# Prova01.net
KiCad netlist of a schematic drawn in EAGLE
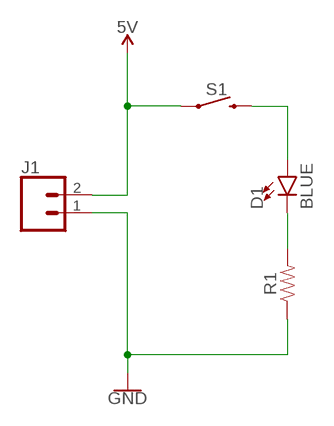
[diagram p0: schematic, sheet 1]

(export (version "E")
  (design (tool "Eeschema 10.0.6"))
  (components
    (comp (ref "D1")
      (value "BLUE")
      (footprint "eagle-import:LED-0603")
      (libsource (lib "eagle-import") (part "LED-BLUE0603"))
    )
    (comp (ref "J1")
      (value "CONN_02")
      (footprint "eagle-import:1X02")
      (libsource (lib "eagle-import") (part "CONN_02"))
    )
    (comp (ref "R1")
      (value "RESISTORAXIAL-0.3")
      (footprint "eagle-import:AXIAL-0.3")
      (libsource (lib "eagle-import") (part "RESISTORAXIAL-0.3"))
    )
    (comp (ref "S1")
      (value "MOMENTARY-SWITCH-SPST-PTH-6.0MM")
      (footprint "eagle-import:TACTILE_SWITCH_PTH_6.0MM")
      (libsource (lib "eagle-import") (part "MOMENTARY-SWITCH-SPST-PTH-6.0MM"))
    )
  )
  (nets
    (net (code "1") (name "5V") (class "Default")
      (node (ref "J1") (pin "2") (pinfunction "2_2") (pintype "passive"))
      (node (ref "S1") (pin "1") (pinfunction "1_1") (pintype "passive"))
    )
    (net (code "2") (name "GND") (class "Default")
      (node (ref "J1") (pin "1") (pinfunction "1_1") (pintype "passive"))
      (node (ref "R1") (pin "P$1") (pinfunction "1_P$1") (pintype "passive"))
    )
    (net (code "3") (name "Net-(R1-2)") (class "Default")
      (node (ref "D1") (pin "C") (pinfunction "C_C") (pintype "passive"))
      (node (ref "R1") (pin "P$2") (pinfunction "2_P$2") (pintype "passive"))
    )
    (net (code "4") (name "Net-(S1-2)") (class "Default")
      (node (ref "D1") (pin "A") (pinfunction "A_A") (pintype "passive"))
      (node (ref "S1") (pin "3") (pinfunction "2_3") (pintype "passive"))
    )
  )
)
